# OctoSlime_Haptics_Module.net
KiCad netlist of a schematic drawn in EasyEDA Pro
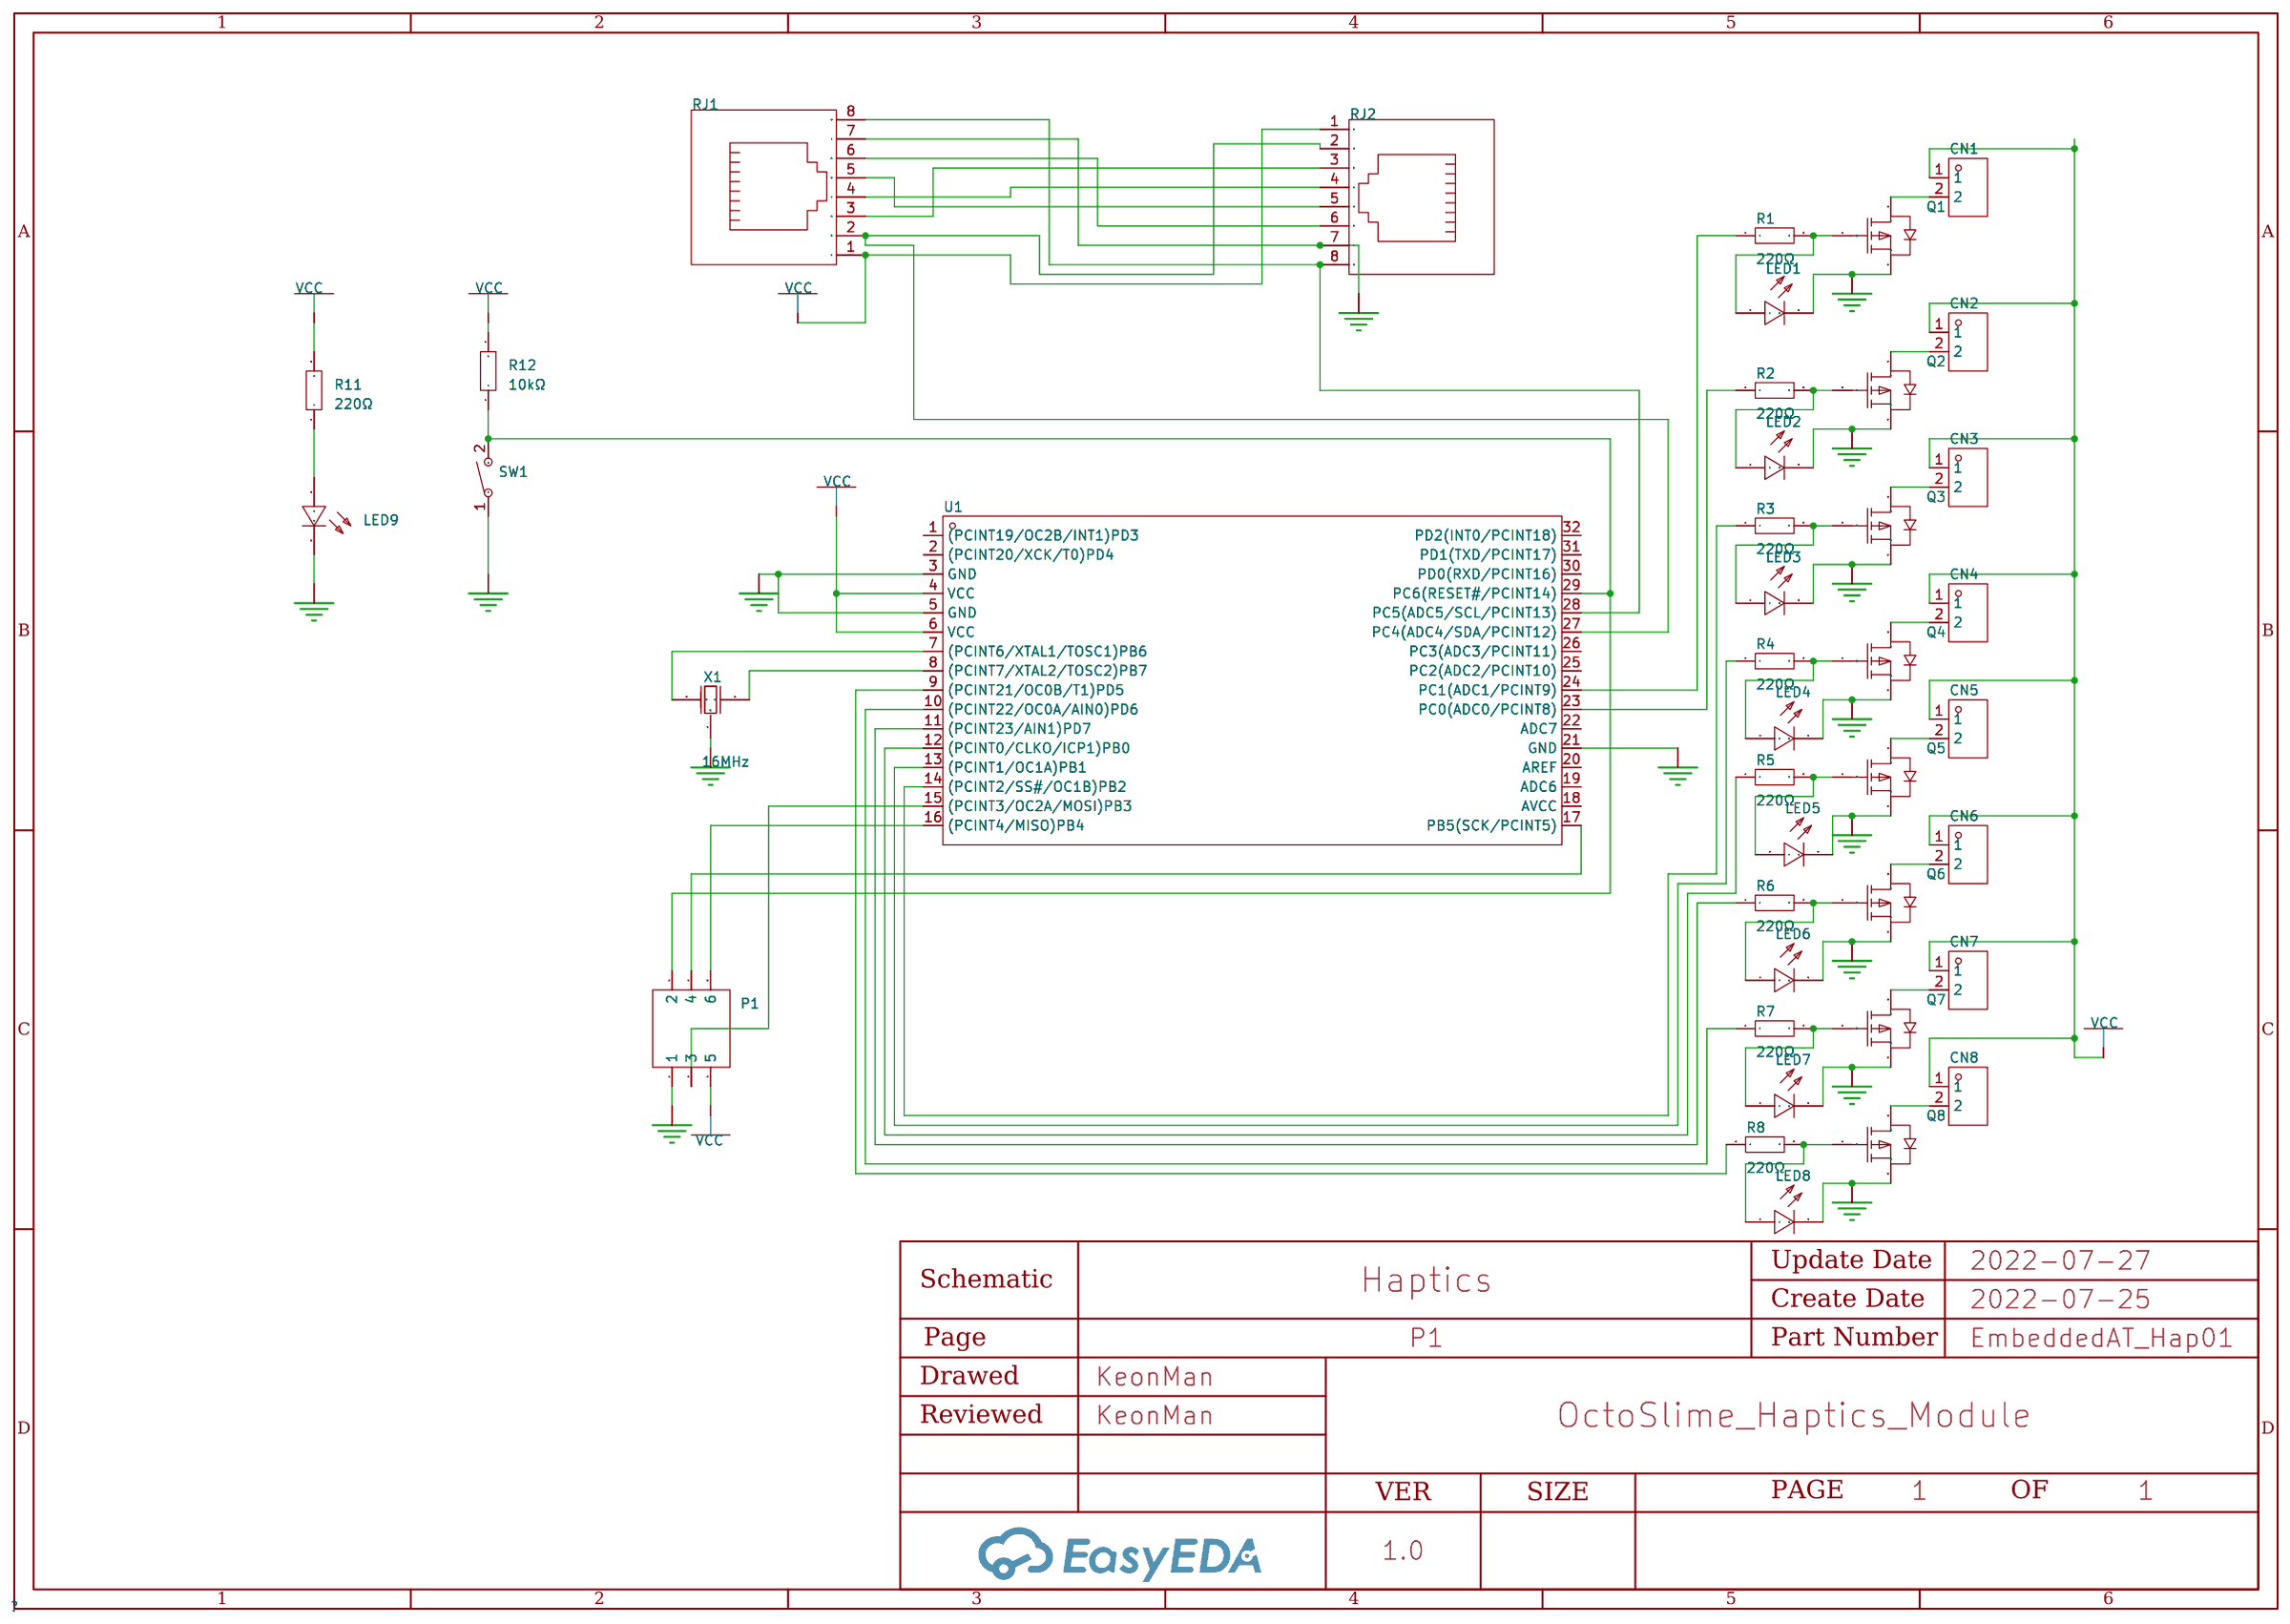
[diagram p0: schematic sheet]

(export (version "E")
  (design (tool "Eeschema 10.0.6"))
  (components
    (comp (ref "CN1")
      (value "~")
      (footprint "easyedapro:CONN-TH_2P-P2.50_HX25003-2WAP")
      (description "俗称： XH2.54 配套：HX25002-2Y")
      (fields (field (name "Manufacturer Part") "HX25003-2WAP") (field (name "Manufacturer") "HX(红星)"))
      (libsource (lib "easyedapro") (part "HX25003-2WAP"))
    )
    (comp (ref "CN2")
      (value "~")
      (footprint "easyedapro:CONN-TH_2P-P2.50_HX25003-2WAP")
      (description "俗称： XH2.54 配套：HX25002-2Y")
      (fields (field (name "Manufacturer Part") "HX25003-2WAP") (field (name "Manufacturer") "HX(红星)"))
      (libsource (lib "easyedapro") (part "HX25003-2WAP"))
    )
    (comp (ref "CN3")
      (value "~")
      (footprint "easyedapro:CONN-TH_2P-P2.50_HX25003-2WAP")
      (description "俗称： XH2.54 配套：HX25002-2Y")
      (fields (field (name "Manufacturer Part") "HX25003-2WAP") (field (name "Manufacturer") "HX(红星)"))
      (libsource (lib "easyedapro") (part "HX25003-2WAP"))
    )
    (comp (ref "CN4")
      (value "~")
      (footprint "easyedapro:CONN-TH_2P-P2.50_HX25003-2WAP")
      (description "俗称： XH2.54 配套：HX25002-2Y")
      (fields (field (name "Manufacturer Part") "HX25003-2WAP") (field (name "Manufacturer") "HX(红星)"))
      (libsource (lib "easyedapro") (part "HX25003-2WAP"))
    )
    (comp (ref "CN5")
      (value "~")
      (footprint "easyedapro:CONN-TH_2P-P2.50_HX25003-2WAP")
      (description "俗称： XH2.54 配套：HX25002-2Y")
      (fields (field (name "Manufacturer Part") "HX25003-2WAP") (field (name "Manufacturer") "HX(红星)"))
      (libsource (lib "easyedapro") (part "HX25003-2WAP"))
    )
    (comp (ref "CN6")
      (value "~")
      (footprint "easyedapro:CONN-TH_2P-P2.50_HX25003-2WAP")
      (description "俗称： XH2.54 配套：HX25002-2Y")
      (fields (field (name "Manufacturer Part") "HX25003-2WAP") (field (name "Manufacturer") "HX(红星)"))
      (libsource (lib "easyedapro") (part "HX25003-2WAP"))
    )
    (comp (ref "CN7")
      (value "~")
      (footprint "easyedapro:CONN-TH_2P-P2.50_HX25003-2WAP")
      (description "俗称： XH2.54 配套：HX25002-2Y")
      (fields (field (name "Manufacturer Part") "HX25003-2WAP") (field (name "Manufacturer") "HX(红星)"))
      (libsource (lib "easyedapro") (part "HX25003-2WAP"))
    )
    (comp (ref "CN8")
      (value "~")
      (footprint "easyedapro:CONN-TH_2P-P2.50_HX25003-2WAP")
      (description "俗称： XH2.54 配套：HX25002-2Y")
      (fields (field (name "Manufacturer Part") "HX25003-2WAP") (field (name "Manufacturer") "HX(红星)"))
      (libsource (lib "easyedapro") (part "HX25003-2WAP"))
    )
    (comp (ref "LED1")
      (value "~")
      (footprint "easyedapro:LED0603-R-RD")
      (description "发光颜色:红灯;")
      (fields
        (field (name "Manufacturer Part") "19-213/R6C-AP1Q2B/3T")
        (field (name "Manufacturer") "EVERLIGHT(台湾亿光)")
      )
      (libsource (lib "easyedapro") (part "19-213/R6C-AP1Q2B/3T_C128051"))
    )
    (comp (ref "LED2")
      (value "~")
      (footprint "easyedapro:LED0603-R-RD")
      (description "发光颜色:红灯;")
      (fields
        (field (name "Manufacturer Part") "19-213/R6C-AP1Q2B/3T")
        (field (name "Manufacturer") "EVERLIGHT(台湾亿光)")
      )
      (libsource (lib "easyedapro") (part "19-213/R6C-AP1Q2B/3T_C128051"))
    )
    (comp (ref "LED3")
      (value "~")
      (footprint "easyedapro:LED0603-R-RD")
      (description "发光颜色:红灯;")
      (fields
        (field (name "Manufacturer Part") "19-213/R6C-AP1Q2B/3T")
        (field (name "Manufacturer") "EVERLIGHT(台湾亿光)")
      )
      (libsource (lib "easyedapro") (part "19-213/R6C-AP1Q2B/3T_C128051"))
    )
    (comp (ref "LED4")
      (value "~")
      (footprint "easyedapro:LED0603-R-RD")
      (description "发光颜色:红灯;")
      (fields
        (field (name "Manufacturer Part") "19-213/R6C-AP1Q2B/3T")
        (field (name "Manufacturer") "EVERLIGHT(台湾亿光)")
      )
      (libsource (lib "easyedapro") (part "19-213/R6C-AP1Q2B/3T_C128051"))
    )
    (comp (ref "LED5")
      (value "~")
      (footprint "easyedapro:LED0603-R-RD")
      (description "发光颜色:红灯;")
      (fields
        (field (name "Manufacturer Part") "19-213/R6C-AP1Q2B/3T")
        (field (name "Manufacturer") "EVERLIGHT(台湾亿光)")
      )
      (libsource (lib "easyedapro") (part "19-213/R6C-AP1Q2B/3T_C128051"))
    )
    (comp (ref "LED6")
      (value "~")
      (footprint "easyedapro:LED0603-R-RD")
      (description "发光颜色:红灯;")
      (fields
        (field (name "Manufacturer Part") "19-213/R6C-AP1Q2B/3T")
        (field (name "Manufacturer") "EVERLIGHT(台湾亿光)")
      )
      (libsource (lib "easyedapro") (part "19-213/R6C-AP1Q2B/3T_C128051"))
    )
    (comp (ref "LED7")
      (value "~")
      (footprint "easyedapro:LED0603-R-RD")
      (description "发光颜色:红灯;")
      (fields
        (field (name "Manufacturer Part") "19-213/R6C-AP1Q2B/3T")
        (field (name "Manufacturer") "EVERLIGHT(台湾亿光)")
      )
      (libsource (lib "easyedapro") (part "19-213/R6C-AP1Q2B/3T_C128051"))
    )
    (comp (ref "LED8")
      (value "~")
      (footprint "easyedapro:LED0603-R-RD")
      (description "发光颜色:红灯;")
      (fields
        (field (name "Manufacturer Part") "19-213/R6C-AP1Q2B/3T")
        (field (name "Manufacturer") "EVERLIGHT(台湾亿光)")
      )
      (libsource (lib "easyedapro") (part "19-213/R6C-AP1Q2B/3T_C128051"))
    )
    (comp (ref "LED9")
      (value "~")
      (footprint "easyedapro:LED0603-R-RD")
      (description "发光颜色:红灯;")
      (fields
        (field (name "Manufacturer Part") "19-213/R6C-AP1Q2B/3T")
        (field (name "Manufacturer") "EVERLIGHT(台湾亿光)")
      )
      (libsource (lib "easyedapro") (part "19-213/R6C-AP1Q2B/3T_C128051"))
    )
    (comp (ref "P1")
      (value "~")
      (footprint "easyedapro:IDC-TH_6P-P2.54_C11214")
      (description "连接器类型:简牛座;间距:2.54mm;排数:2;行距:2.54mm;封装形式:直插;触头材质:黄铜;触头镀层:金;")
      (fields (field (name "Manufacturer Part") "2.54-2*3P简牛") (field (name "Manufacturer") "BOOMELE(博穆精密)"))
      (libsource (lib "easyedapro") (part "HDR-IDC-2.54-2X3P"))
    )
    (comp (ref "Q1")
      (value "~")
      (footprint "easyedapro:SC-70-3_L2.2-W1.2-P1.30-LS2.1-BL")
      (fields (field (name "Manufacturer Part") "CJ2101") (field (name "Manufacturer") "CJ（江苏长电/长晶）"))
      (libsource (lib "easyedapro") (part "CJ2101"))
    )
    (comp (ref "Q2")
      (value "~")
      (footprint "easyedapro:SC-70-3_L2.2-W1.2-P1.30-LS2.1-BL")
      (fields (field (name "Manufacturer Part") "CJ2101") (field (name "Manufacturer") "CJ（江苏长电/长晶）"))
      (libsource (lib "easyedapro") (part "CJ2101"))
    )
    (comp (ref "Q3")
      (value "~")
      (footprint "easyedapro:SC-70-3_L2.2-W1.2-P1.30-LS2.1-BL")
      (fields (field (name "Manufacturer Part") "CJ2101") (field (name "Manufacturer") "CJ（江苏长电/长晶）"))
      (libsource (lib "easyedapro") (part "CJ2101"))
    )
    (comp (ref "Q4")
      (value "~")
      (footprint "easyedapro:SC-70-3_L2.2-W1.2-P1.30-LS2.1-BL")
      (fields (field (name "Manufacturer Part") "CJ2101") (field (name "Manufacturer") "CJ（江苏长电/长晶）"))
      (libsource (lib "easyedapro") (part "CJ2101"))
    )
    (comp (ref "Q5")
      (value "~")
      (footprint "easyedapro:SC-70-3_L2.2-W1.2-P1.30-LS2.1-BL")
      (fields (field (name "Manufacturer Part") "CJ2101") (field (name "Manufacturer") "CJ（江苏长电/长晶）"))
      (libsource (lib "easyedapro") (part "CJ2101"))
    )
    (comp (ref "Q6")
      (value "~")
      (footprint "easyedapro:SC-70-3_L2.2-W1.2-P1.30-LS2.1-BL")
      (fields (field (name "Manufacturer Part") "CJ2101") (field (name "Manufacturer") "CJ（江苏长电/长晶）"))
      (libsource (lib "easyedapro") (part "CJ2101"))
    )
    (comp (ref "Q7")
      (value "~")
      (footprint "easyedapro:SC-70-3_L2.2-W1.2-P1.30-LS2.1-BL")
      (fields (field (name "Manufacturer Part") "CJ2101") (field (name "Manufacturer") "CJ（江苏长电/长晶）"))
      (libsource (lib "easyedapro") (part "CJ2101"))
    )
    (comp (ref "Q8")
      (value "~")
      (footprint "easyedapro:SC-70-3_L2.2-W1.2-P1.30-LS2.1-BL")
      (fields (field (name "Manufacturer Part") "CJ2101") (field (name "Manufacturer") "CJ（江苏长电/长晶）"))
      (libsource (lib "easyedapro") (part "CJ2101"))
    )
    (comp (ref "R1")
      (value "220Ω")
      (footprint "easyedapro:R1206")
      (description "电阻类型:厚膜电阻;阻值:220Ω;精度:±1%;功率:250mW;温度系数:±100ppm/;最大工作电压:200V;工作温度范围:-55~+155;")
      (fields (field (name "Manufacturer Part") "RC1206FR-07220RL") (field (name "Manufacturer") "YAGEO(国巨)"))
      (libsource (lib "easyedapro") (part "RC1206FR-07220RL"))
    )
    (comp (ref "R2")
      (value "220Ω")
      (footprint "easyedapro:R1206")
      (description "电阻类型:厚膜电阻;阻值:220Ω;精度:±1%;功率:250mW;温度系数:±100ppm/;最大工作电压:200V;工作温度范围:-55~+155;")
      (fields (field (name "Manufacturer Part") "RC1206FR-07220RL") (field (name "Manufacturer") "YAGEO(国巨)"))
      (libsource (lib "easyedapro") (part "RC1206FR-07220RL"))
    )
    (comp (ref "R3")
      (value "220Ω")
      (footprint "easyedapro:R1206")
      (description "电阻类型:厚膜电阻;阻值:220Ω;精度:±1%;功率:250mW;温度系数:±100ppm/;最大工作电压:200V;工作温度范围:-55~+155;")
      (fields (field (name "Manufacturer Part") "RC1206FR-07220RL") (field (name "Manufacturer") "YAGEO(国巨)"))
      (libsource (lib "easyedapro") (part "RC1206FR-07220RL"))
    )
    (comp (ref "R4")
      (value "220Ω")
      (footprint "easyedapro:R1206")
      (description "电阻类型:厚膜电阻;阻值:220Ω;精度:±1%;功率:250mW;温度系数:±100ppm/;最大工作电压:200V;工作温度范围:-55~+155;")
      (fields (field (name "Manufacturer Part") "RC1206FR-07220RL") (field (name "Manufacturer") "YAGEO(国巨)"))
      (libsource (lib "easyedapro") (part "RC1206FR-07220RL"))
    )
    (comp (ref "R5")
      (value "220Ω")
      (footprint "easyedapro:R1206")
      (description "电阻类型:厚膜电阻;阻值:220Ω;精度:±1%;功率:250mW;温度系数:±100ppm/;最大工作电压:200V;工作温度范围:-55~+155;")
      (fields (field (name "Manufacturer Part") "RC1206FR-07220RL") (field (name "Manufacturer") "YAGEO(国巨)"))
      (libsource (lib "easyedapro") (part "RC1206FR-07220RL"))
    )
    (comp (ref "R6")
      (value "220Ω")
      (footprint "easyedapro:R1206")
      (description "电阻类型:厚膜电阻;阻值:220Ω;精度:±1%;功率:250mW;温度系数:±100ppm/;最大工作电压:200V;工作温度范围:-55~+155;")
      (fields (field (name "Manufacturer Part") "RC1206FR-07220RL") (field (name "Manufacturer") "YAGEO(国巨)"))
      (libsource (lib "easyedapro") (part "RC1206FR-07220RL"))
    )
    (comp (ref "R7")
      (value "220Ω")
      (footprint "easyedapro:R1206")
      (description "电阻类型:厚膜电阻;阻值:220Ω;精度:±1%;功率:250mW;温度系数:±100ppm/;最大工作电压:200V;工作温度范围:-55~+155;")
      (fields (field (name "Manufacturer Part") "RC1206FR-07220RL") (field (name "Manufacturer") "YAGEO(国巨)"))
      (libsource (lib "easyedapro") (part "RC1206FR-07220RL"))
    )
    (comp (ref "R8")
      (value "220Ω")
      (footprint "easyedapro:R1206")
      (description "电阻类型:厚膜电阻;阻值:220Ω;精度:±1%;功率:250mW;温度系数:±100ppm/;最大工作电压:200V;工作温度范围:-55~+155;")
      (fields (field (name "Manufacturer Part") "RC1206FR-07220RL") (field (name "Manufacturer") "YAGEO(国巨)"))
      (libsource (lib "easyedapro") (part "RC1206FR-07220RL"))
    )
    (comp (ref "R11")
      (value "220Ω")
      (footprint "easyedapro:R1206")
      (description "电阻类型:厚膜电阻;阻值:220Ω;精度:±1%;功率:250mW;温度系数:±100ppm/;最大工作电压:200V;工作温度范围:-55~+155;")
      (fields (field (name "Manufacturer Part") "RC1206FR-07220RL") (field (name "Manufacturer") "YAGEO(国巨)"))
      (libsource (lib "easyedapro") (part "RC1206FR-07220RL"))
    )
    (comp (ref "R12")
      (value "10kΩ")
      (footprint "easyedapro:R0805")
      (description "电阻类型:厚膜电阻;阻值:10kΩ;精度:±1%;功率:125mW;温度系数:-;最大工作电压:150V;工作温度范围:-55~+125;")
      (fields
        (field (name "Manufacturer Part") "RMCF0805FT10K0")
        (field (name "Manufacturer") "SEI(Stackpole Electronics Inc.)")
      )
      (libsource (lib "easyedapro") (part "RMCF0805FT10K0"))
    )
    (comp (ref "RJ1")
      (value "~")
      (footprint "easyedapro:RJ45-TH_R-RJ45R08P-A004")
      (description "连接器类型:RJ插座;USOC代码:RJ45;端口数量:1;等级:-;安装方式:弯插;屏蔽:无;LED:无;工作温度范围:0~+70;")
      (fields (field (name "Manufacturer Part") "R-RJ45R08P-A004") (field (name "Manufacturer") "Ckmtw(灿科盟)"))
      (libsource (lib "easyedapro") (part "R-RJ45R08P-A004"))
    )
    (comp (ref "RJ2")
      (value "~")
      (footprint "easyedapro:RJ45-TH_R-RJ45R08P-A004")
      (description "连接器类型:RJ插座;USOC代码:RJ45;端口数量:1;等级:-;安装方式:弯插;屏蔽:无;LED:无;工作温度范围:0~+70;")
      (fields (field (name "Manufacturer Part") "R-RJ45R08P-A004") (field (name "Manufacturer") "Ckmtw(灿科盟)"))
      (libsource (lib "easyedapro") (part "R-RJ45R08P-A004"))
    )
    (comp (ref "SW1")
      (value "~")
      (footprint "easyedapro:SW-SMD_L4.0-W2.9-LS5.0")
      (fields (field (name "Manufacturer Part") "TS342A2P-WZ") (field (name "Manufacturer") "SHOU HAN(首韩)"))
      (libsource (lib "easyedapro") (part "TS342A2P-WZ"))
    )
    (comp (ref "U1")
      (value "~")
      (footprint "easyedapro:TQFP-32_L7.0-W7.0-P0.80-LS9.0-BL")
      (description "CPU内核:AVR;主频（MAX):20MHz;工作电压:1.8V ~ 5.5V;")
      (fields
        (field (name "Manufacturer Part") "ATMEGA328P-AU")
        (field (name "Manufacturer") "MICROCHIP(美国微芯)")
      )
      (libsource (lib "easyedapro") (part "ATMEGA328P-AU"))
    )
    (comp (ref "X1")
      (value "16MHz")
      (footprint "easyedapro:OSC-SMD_3P-L3.2-W1.3-P1.2-L")
      (description "频率:16MHz;频率容差:±0.5%;内藏负载电容:15pF;谐振阻抗:40Ω;")
      (fields
        (field (name "Manufacturer Part") "CSTNE16M0V530000R0")
        (field (name "Manufacturer") "muRata(村田)")
      )
      (libsource (lib "easyedapro") (part "CSTNE16M0V530000R0"))
    )
  )
  (nets
    (net (code "1") (name "GND") (class "Default")
      (node (ref "LED1") (pin "2") (pinfunction "C_2") (pintype "input"))
      (node (ref "LED2") (pin "2") (pinfunction "C_2") (pintype "input"))
      (node (ref "LED3") (pin "2") (pinfunction "C_2") (pintype "input"))
      (node (ref "LED4") (pin "2") (pinfunction "C_2") (pintype "input"))
      (node (ref "LED5") (pin "2") (pinfunction "C_2") (pintype "input"))
      (node (ref "LED6") (pin "2") (pinfunction "C_2") (pintype "input"))
      (node (ref "LED7") (pin "2") (pinfunction "C_2") (pintype "input"))
      (node (ref "LED8") (pin "2") (pinfunction "C_2") (pintype "input"))
      (node (ref "LED9") (pin "2") (pinfunction "C_2") (pintype "input"))
      (node (ref "P1") (pin "1") (pinfunction "1_1") (pintype "input"))
      (node (ref "Q1") (pin "2") (pinfunction "S_2") (pintype "input"))
      (node (ref "Q2") (pin "2") (pinfunction "S_2") (pintype "input"))
      (node (ref "Q3") (pin "2") (pinfunction "S_2") (pintype "input"))
      (node (ref "Q4") (pin "2") (pinfunction "S_2") (pintype "input"))
      (node (ref "Q5") (pin "2") (pinfunction "S_2") (pintype "input"))
      (node (ref "Q6") (pin "2") (pinfunction "S_2") (pintype "input"))
      (node (ref "Q7") (pin "2") (pinfunction "S_2") (pintype "input"))
      (node (ref "Q8") (pin "2") (pinfunction "S_2") (pintype "input"))
      (node (ref "RJ1") (pin "7") (pinfunction "7_7") (pintype "input"))
      (node (ref "RJ2") (pin "7") (pinfunction "7_7") (pintype "input"))
      (node (ref "SW1") (pin "1") (pinfunction "1_1") (pintype "input"))
      (node (ref "U1") (pin "21") (pinfunction "GND_21") (pintype "input"))
      (node (ref "U1") (pin "3") (pinfunction "GND_3") (pintype "input"))
      (node (ref "U1") (pin "5") (pinfunction "GND_5") (pintype "input"))
      (node (ref "X1") (pin "2") (pinfunction "GND_2") (pintype "input"))
    )
    (net (code "2") (name "Net-(LED1-A)") (class "Default")
      (node (ref "LED1") (pin "1") (pinfunction "A_1") (pintype "input"))
      (node (ref "Q1") (pin "1") (pinfunction "G_1") (pintype "input"))
      (node (ref "R1") (pin "2") (pinfunction "2_2") (pintype "input"))
    )
    (net (code "3") (name "Net-(LED2-A)") (class "Default")
      (node (ref "LED2") (pin "1") (pinfunction "A_1") (pintype "input"))
      (node (ref "Q2") (pin "1") (pinfunction "G_1") (pintype "input"))
      (node (ref "R2") (pin "2") (pinfunction "2_2") (pintype "input"))
    )
    (net (code "4") (name "Net-(LED3-A)") (class "Default")
      (node (ref "LED3") (pin "1") (pinfunction "A_1") (pintype "input"))
      (node (ref "Q3") (pin "1") (pinfunction "G_1") (pintype "input"))
      (node (ref "R3") (pin "2") (pinfunction "2_2") (pintype "input"))
    )
    (net (code "5") (name "Net-(LED4-A)") (class "Default")
      (node (ref "LED4") (pin "1") (pinfunction "A_1") (pintype "input"))
      (node (ref "Q4") (pin "1") (pinfunction "G_1") (pintype "input"))
      (node (ref "R4") (pin "2") (pinfunction "2_2") (pintype "input"))
    )
    (net (code "6") (name "Net-(LED5-A)") (class "Default")
      (node (ref "LED5") (pin "1") (pinfunction "A_1") (pintype "input"))
      (node (ref "Q5") (pin "1") (pinfunction "G_1") (pintype "input"))
      (node (ref "R5") (pin "2") (pinfunction "2_2") (pintype "input"))
    )
    (net (code "7") (name "Net-(LED6-A)") (class "Default")
      (node (ref "LED6") (pin "1") (pinfunction "A_1") (pintype "input"))
      (node (ref "Q6") (pin "1") (pinfunction "G_1") (pintype "input"))
      (node (ref "R6") (pin "2") (pinfunction "2_2") (pintype "input"))
    )
    (net (code "8") (name "Net-(LED7-A)") (class "Default")
      (node (ref "LED7") (pin "1") (pinfunction "A_1") (pintype "input"))
      (node (ref "Q7") (pin "1") (pinfunction "G_1") (pintype "input"))
      (node (ref "R7") (pin "2") (pinfunction "2_2") (pintype "input"))
    )
    (net (code "9") (name "Net-(LED8-A)") (class "Default")
      (node (ref "LED8") (pin "1") (pinfunction "A_1") (pintype "input"))
      (node (ref "Q8") (pin "1") (pinfunction "G_1") (pintype "input"))
      (node (ref "R8") (pin "2") (pinfunction "2_2") (pintype "input"))
    )
    (net (code "10") (name "Net-(LED9-A)") (class "Default")
      (node (ref "LED9") (pin "1") (pinfunction "A_1") (pintype "input"))
      (node (ref "R11") (pin "1") (pinfunction "1_1") (pintype "input"))
    )
    (net (code "11") (name "Net-(Q1-D)") (class "Default")
      (node (ref "CN1") (pin "2") (pinfunction "2_2") (pintype "input"))
      (node (ref "Q1") (pin "3") (pinfunction "D_3") (pintype "input"))
    )
    (net (code "12") (name "Net-(Q2-D)") (class "Default")
      (node (ref "CN2") (pin "2") (pinfunction "2_2") (pintype "input"))
      (node (ref "Q2") (pin "3") (pinfunction "D_3") (pintype "input"))
    )
    (net (code "13") (name "Net-(Q3-D)") (class "Default")
      (node (ref "CN3") (pin "2") (pinfunction "2_2") (pintype "input"))
      (node (ref "Q3") (pin "3") (pinfunction "D_3") (pintype "input"))
    )
    (net (code "14") (name "Net-(Q4-D)") (class "Default")
      (node (ref "CN4") (pin "2") (pinfunction "2_2") (pintype "input"))
      (node (ref "Q4") (pin "3") (pinfunction "D_3") (pintype "input"))
    )
    (net (code "15") (name "Net-(Q5-D)") (class "Default")
      (node (ref "CN5") (pin "2") (pinfunction "2_2") (pintype "input"))
      (node (ref "Q5") (pin "3") (pinfunction "D_3") (pintype "input"))
    )
    (net (code "16") (name "Net-(Q6-D)") (class "Default")
      (node (ref "CN6") (pin "2") (pinfunction "2_2") (pintype "input"))
      (node (ref "Q6") (pin "3") (pinfunction "D_3") (pintype "input"))
    )
    (net (code "17") (name "Net-(Q7-D)") (class "Default")
      (node (ref "CN7") (pin "2") (pinfunction "2_2") (pintype "input"))
      (node (ref "Q7") (pin "3") (pinfunction "D_3") (pintype "input"))
    )
    (net (code "18") (name "Net-(Q8-D)") (class "Default")
      (node (ref "CN8") (pin "2") (pinfunction "2_2") (pintype "input"))
      (node (ref "Q8") (pin "3") (pinfunction "D_3") (pintype "input"))
    )
    (net (code "19") (name "Net-(RJ1-Pad3)") (class "Default")
      (node (ref "RJ1") (pin "3") (pinfunction "3_3") (pintype "input"))
      (node (ref "RJ2") (pin "3") (pinfunction "3_3") (pintype "input"))
    )
    (net (code "20") (name "Net-(RJ1-Pad4)") (class "Default")
      (node (ref "RJ1") (pin "4") (pinfunction "4_4") (pintype "input"))
      (node (ref "RJ2") (pin "4") (pinfunction "4_4") (pintype "input"))
    )
    (net (code "21") (name "Net-(RJ1-Pad5)") (class "Default")
      (node (ref "RJ1") (pin "5") (pinfunction "5_5") (pintype "input"))
      (node (ref "RJ2") (pin "5") (pinfunction "5_5") (pintype "input"))
    )
    (net (code "22") (name "Net-(RJ1-Pad6)") (class "Default")
      (node (ref "RJ1") (pin "6") (pinfunction "6_6") (pintype "input"))
      (node (ref "RJ2") (pin "6") (pinfunction "6_6") (pintype "input"))
    )
    (net (code "23") (name "Net-(U1-(PCINT0{slash}CLKO{slash}ICP1)PB0)") (class "Default")
      (node (ref "R5") (pin "1") (pinfunction "1_1") (pintype "input"))
      (node (ref "U1") (pin "12") (pinfunction "(PCINT0/CLKO/ICP1)PB0_12") (pintype "input"))
    )
    (net (code "24") (name "Net-(U1-(PCINT1{slash}OC1A)PB1)") (class "Default")
      (node (ref "R4") (pin "1") (pinfunction "1_1") (pintype "input"))
      (node (ref "U1") (pin "13") (pinfunction "(PCINT1/OC1A)PB1_13") (pintype "input"))
    )
    (net (code "25") (name "Net-(U1-(PCINT2{slash}SS#{slash}OC1B)PB2)") (class "Default")
      (node (ref "R3") (pin "1") (pinfunction "1_1") (pintype "input"))
      (node (ref "U1") (pin "14") (pinfunction "(PCINT2/SS#/OC1B)PB2_14") (pintype "input"))
    )
    (net (code "26") (name "Net-(U1-(PCINT3{slash}OC2A{slash}MOSI)PB3)") (class "Default")
      (node (ref "P1") (pin "3") (pinfunction "3_3") (pintype "input"))
      (node (ref "U1") (pin "15") (pinfunction "(PCINT3/OC2A/MOSI)PB3_15") (pintype "input"))
    )
    (net (code "27") (name "Net-(U1-(PCINT4{slash}MISO)PB4)") (class "Default")
      (node (ref "P1") (pin "6") (pinfunction "6_6") (pintype "input"))
      (node (ref "U1") (pin "16") (pinfunction "(PCINT4/MISO)PB4_16") (pintype "input"))
    )
    (net (code "28") (name "Net-(U1-(PCINT6{slash}XTAL1{slash}TOSC1)PB6)") (class "Default")
      (node (ref "U1") (pin "7") (pinfunction "(PCINT6/XTAL1/TOSC1)PB6_7") (pintype "input"))
      (node (ref "X1") (pin "3") (pinfunction "OSC2_3") (pintype "input"))
    )
    (net (code "29") (name "Net-(U1-(PCINT7{slash}XTAL2{slash}TOSC2)PB7)") (class "Default")
      (node (ref "U1") (pin "8") (pinfunction "(PCINT7/XTAL2/TOSC2)PB7_8") (pintype "input"))
      (node (ref "X1") (pin "1") (pinfunction "OSC1_1") (pintype "input"))
    )
    (net (code "30") (name "Net-(U1-(PCINT21{slash}OC0B{slash}T1)PD5)") (class "Default")
      (node (ref "R8") (pin "1") (pinfunction "1_1") (pintype "input"))
      (node (ref "U1") (pin "9") (pinfunction "(PCINT21/OC0B/T1)PD5_9") (pintype "input"))
    )
    (net (code "31") (name "Net-(U1-(PCINT22{slash}OC0A{slash}AIN0)PD6)") (class "Default")
      (node (ref "R7") (pin "1") (pinfunction "1_1") (pintype "input"))
      (node (ref "U1") (pin "10") (pinfunction "(PCINT22/OC0A/AIN0)PD6_10") (pintype "input"))
    )
    (net (code "32") (name "Net-(U1-(PCINT23{slash}AIN1)PD7)") (class "Default")
      (node (ref "R6") (pin "1") (pinfunction "1_1") (pintype "input"))
      (node (ref "U1") (pin "11") (pinfunction "(PCINT23/AIN1)PD7_11") (pintype "input"))
    )
    (net (code "33") (name "Net-(U1-PB5(SCK{slash}PCINT5))") (class "Default")
      (node (ref "P1") (pin "4") (pinfunction "4_4") (pintype "input"))
      (node (ref "U1") (pin "17") (pinfunction "PB5(SCK/PCINT5)_17") (pintype "input"))
    )
    (net (code "34") (name "Net-(U1-PC0(ADC0{slash}PCINT8))") (class "Default")
      (node (ref "R2") (pin "1") (pinfunction "1_1") (pintype "input"))
      (node (ref "U1") (pin "23") (pinfunction "PC0(ADC0/PCINT8)_23") (pintype "input"))
    )
    (net (code "35") (name "Net-(U1-PC1(ADC1{slash}PCINT9))") (class "Default")
      (node (ref "R1") (pin "1") (pinfunction "1_1") (pintype "input"))
      (node (ref "U1") (pin "24") (pinfunction "PC1(ADC1/PCINT9)_24") (pintype "input"))
    )
    (net (code "36") (name "Net-(U1-PC4(ADC4{slash}SDA{slash}PCINT12))") (class "Default")
      (node (ref "RJ1") (pin "2") (pinfunction "2_2") (pintype "input"))
      (node (ref "RJ2") (pin "2") (pinfunction "2_2") (pintype "input"))
      (node (ref "U1") (pin "27") (pinfunction "PC4(ADC4/SDA/PCINT12)_27") (pintype "input"))
    )
    (net (code "37") (name "Net-(U1-PC5(ADC5{slash}SCL{slash}PCINT13))") (class "Default")
      (node (ref "RJ1") (pin "8") (pinfunction "8_8") (pintype "input"))
      (node (ref "RJ2") (pin "8") (pinfunction "8_8") (pintype "input"))
      (node (ref "U1") (pin "28") (pinfunction "PC5(ADC5/SCL/PCINT13)_28") (pintype "input"))
    )
    (net (code "38") (name "Net-(U1-PC6(RESET#{slash}PCINT14))") (class "Default")
      (node (ref "P1") (pin "2") (pinfunction "2_2") (pintype "input"))
      (node (ref "R12") (pin "1") (pinfunction "1_1") (pintype "input"))
      (node (ref "SW1") (pin "2") (pinfunction "2_2") (pintype "input"))
      (node (ref "U1") (pin "29") (pinfunction "PC6(RESET#/PCINT14)_29") (pintype "input"))
    )
    (net (code "39") (name "VCC") (class "Default")
      (node (ref "CN1") (pin "1") (pinfunction "1_1") (pintype "input"))
      (node (ref "CN2") (pin "1") (pinfunction "1_1") (pintype "input"))
      (node (ref "CN3") (pin "1") (pinfunction "1_1") (pintype "input"))
      (node (ref "CN4") (pin "1") (pinfunction "1_1") (pintype "input"))
      (node (ref "CN5") (pin "1") (pinfunction "1_1") (pintype "input"))
      (node (ref "CN6") (pin "1") (pinfunction "1_1") (pintype "input"))
      (node (ref "CN7") (pin "1") (pinfunction "1_1") (pintype "input"))
      (node (ref "CN8") (pin "1") (pinfunction "1_1") (pintype "input"))
      (node (ref "P1") (pin "5") (pinfunction "5_5") (pintype "input"))
      (node (ref "R11") (pin "2") (pinfunction "2_2") (pintype "input"))
      (node (ref "R12") (pin "2") (pinfunction "2_2") (pintype "input"))
      (node (ref "RJ1") (pin "1") (pinfunction "1_1") (pintype "input"))
      (node (ref "RJ2") (pin "1") (pinfunction "1_1") (pintype "input"))
      (node (ref "U1") (pin "4") (pinfunction "VCC_4") (pintype "input"))
      (node (ref "U1") (pin "6") (pinfunction "VCC_6") (pintype "input"))
    )
    (net (code "40") (name "unconnected-(U1-(PCINT19{slash}OC2B{slash}INT1)PD3-Pad1)") (class "Default")
      (node (ref "U1") (pin "1") (pinfunction "(PCINT19/OC2B/INT1)PD3_1") (pintype "input"))
    )
    (net (code "41") (name "unconnected-(U1-(PCINT20{slash}XCK{slash}T0)PD4-Pad2)") (class "Default")
      (node (ref "U1") (pin "2") (pinfunction "(PCINT20/XCK/T0)PD4_2") (pintype "input"))
    )
    (net (code "42") (name "unconnected-(U1-ADC6-Pad19)") (class "Default")
      (node (ref "U1") (pin "19") (pinfunction "ADC6_19") (pintype "input"))
    )
    (net (code "43") (name "unconnected-(U1-ADC7-Pad22)") (class "Default")
      (node (ref "U1") (pin "22") (pinfunction "ADC7_22") (pintype "input"))
    )
    (net (code "44") (name "unconnected-(U1-AREF-Pad20)") (class "Default")
      (node (ref "U1") (pin "20") (pinfunction "AREF_20") (pintype "input"))
    )
    (net (code "45") (name "unconnected-(U1-AVCC-Pad18)") (class "Default")
      (node (ref "U1") (pin "18") (pinfunction "AVCC_18") (pintype "input"))
    )
    (net (code "46") (name "unconnected-(U1-PC2(ADC2{slash}PCINT10)-Pad25)") (class "Default")
      (node (ref "U1") (pin "25") (pinfunction "PC2(ADC2/PCINT10)_25") (pintype "input"))
    )
    (net (code "47") (name "unconnected-(U1-PC3(ADC3{slash}PCINT11)-Pad26)") (class "Default")
      (node (ref "U1") (pin "26") (pinfunction "PC3(ADC3/PCINT11)_26") (pintype "input"))
    )
    (net (code "48") (name "unconnected-(U1-PD0(RXD{slash}PCINT16)-Pad30)") (class "Default")
      (node (ref "U1") (pin "30") (pinfunction "PD0(RXD/PCINT16)_30") (pintype "input"))
    )
    (net (code "49") (name "unconnected-(U1-PD1(TXD{slash}PCINT17)-Pad31)") (class "Default")
      (node (ref "U1") (pin "31") (pinfunction "PD1(TXD/PCINT17)_31") (pintype "input"))
    )
    (net (code "50") (name "unconnected-(U1-PD2(INT0{slash}PCINT18)-Pad32)") (class "Default")
      (node (ref "U1") (pin "32") (pinfunction "PD2(INT0/PCINT18)_32") (pintype "input"))
    )
  )
)
